# controllera.net
KiCad netlist of a schematic drawn in EAGLE
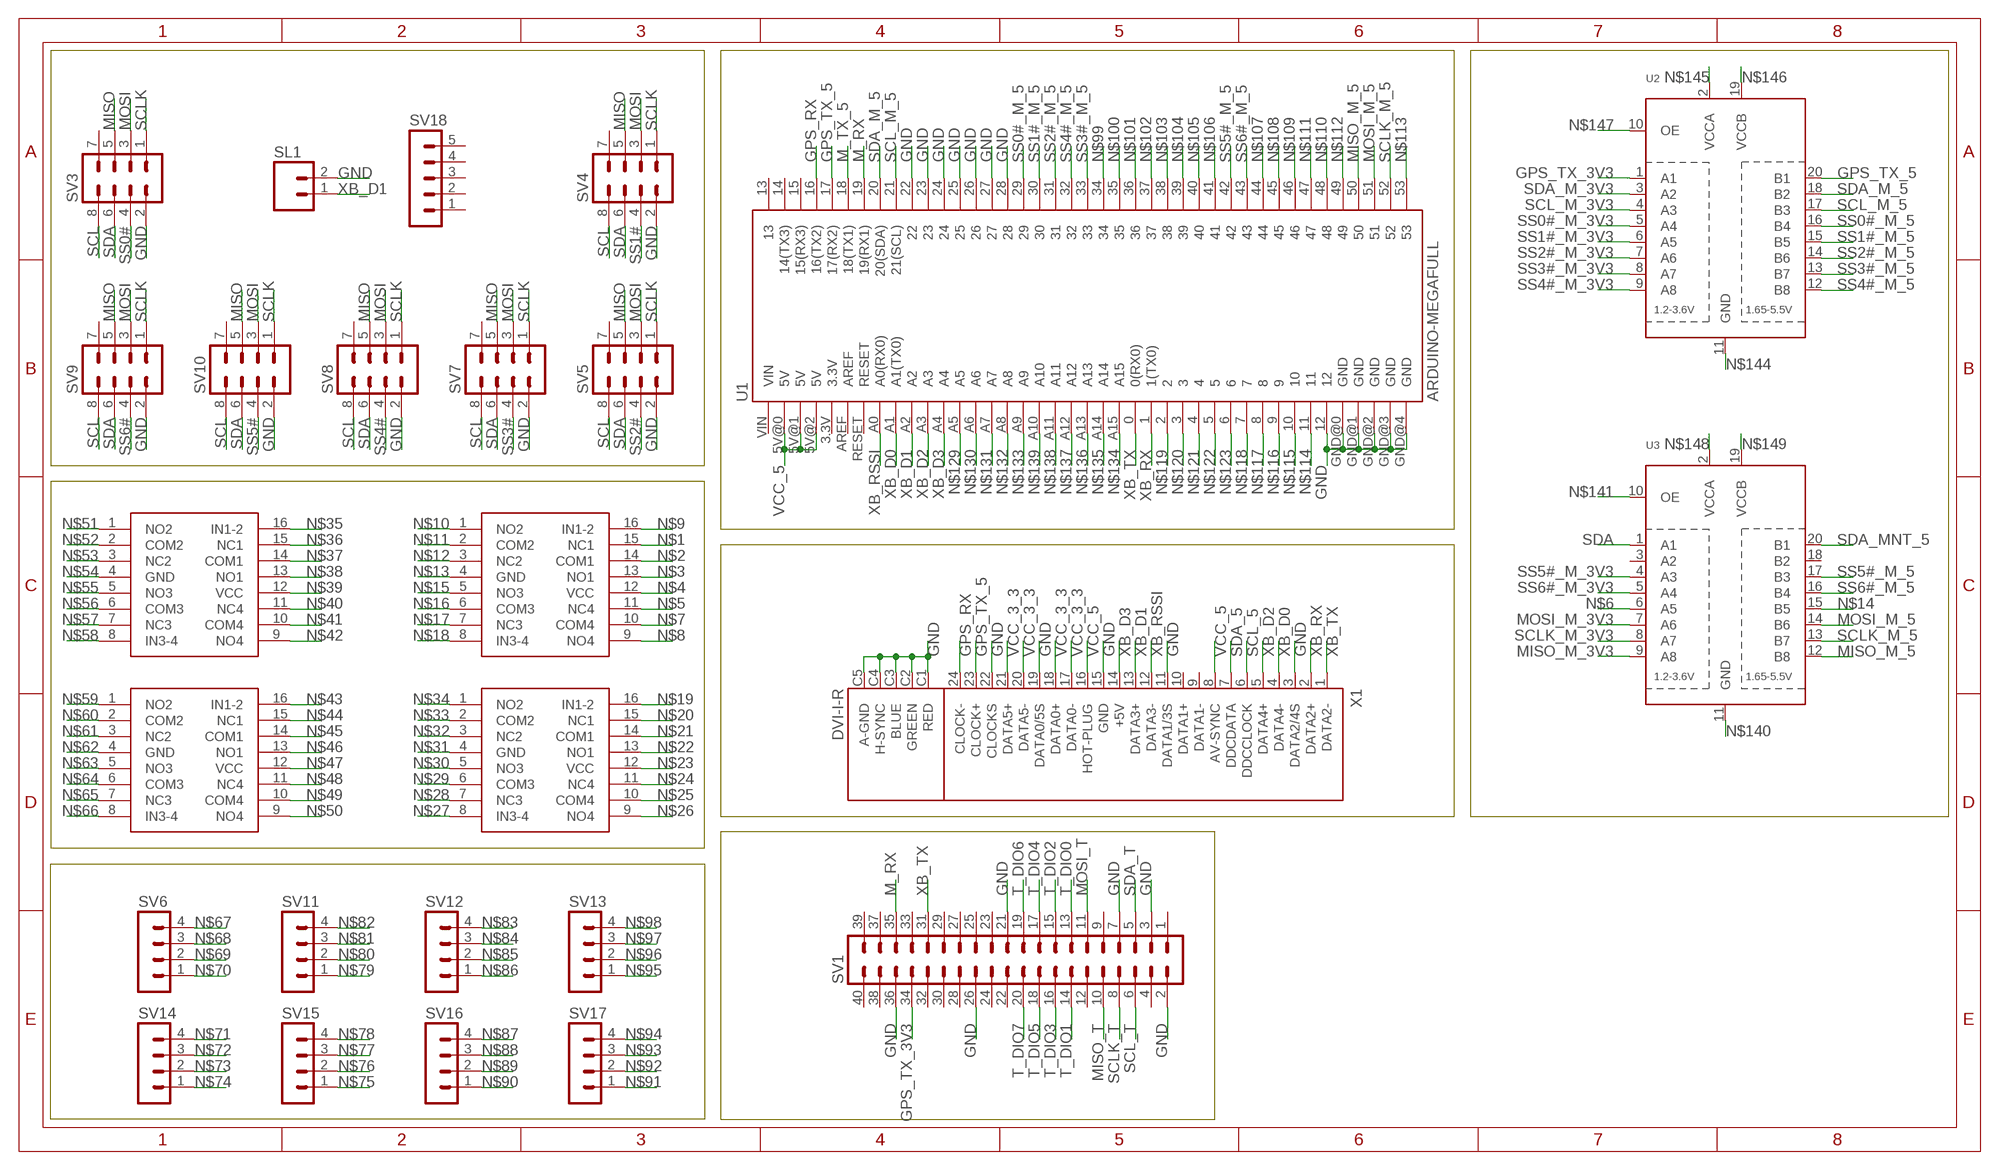
[diagram p0: schematic, sheet 1]

(export (version "E")
  (design (tool "Eeschema 10.0.6"))
  (components
    (comp (ref "SL1")
      (value "MA02")
      (footprint "eagle-import:02PA")
      (libsource (lib "eagle-import") (part "MA02"))
    )
    (comp (ref "SV1")
      (value "MA20-2")
      (footprint "eagle-import:MA20-2")
      (libsource (lib "eagle-import") (part "MA20-2"))
    )
    (comp (ref "SV3")
      (value "MA04-2")
      (footprint "eagle-import:MA04-2")
      (libsource (lib "eagle-import") (part "MA04-2"))
    )
    (comp (ref "SV4")
      (value "MA04-2")
      (footprint "eagle-import:MA04-2")
      (libsource (lib "eagle-import") (part "MA04-2"))
    )
    (comp (ref "SV5")
      (value "MA04-2")
      (footprint "eagle-import:MA04-2")
      (libsource (lib "eagle-import") (part "MA04-2"))
    )
    (comp (ref "SV6")
      (value "MA04-1")
      (footprint "eagle-import:MA04-1")
      (libsource (lib "eagle-import") (part "MA04-1"))
    )
    (comp (ref "SV7")
      (value "MA04-2")
      (footprint "eagle-import:MA04-2")
      (libsource (lib "eagle-import") (part "MA04-2"))
    )
    (comp (ref "SV8")
      (value "MA04-2")
      (footprint "eagle-import:MA04-2")
      (libsource (lib "eagle-import") (part "MA04-2"))
    )
    (comp (ref "SV9")
      (value "MA04-2")
      (footprint "eagle-import:MA04-2")
      (libsource (lib "eagle-import") (part "MA04-2"))
    )
    (comp (ref "SV10")
      (value "MA04-2")
      (footprint "eagle-import:MA04-2")
      (libsource (lib "eagle-import") (part "MA04-2"))
    )
    (comp (ref "SV11")
      (value "MA04-1")
      (footprint "eagle-import:MA04-1")
      (libsource (lib "eagle-import") (part "MA04-1"))
    )
    (comp (ref "SV12")
      (value "MA04-1")
      (footprint "eagle-import:MA04-1")
      (libsource (lib "eagle-import") (part "MA04-1"))
    )
    (comp (ref "SV13")
      (value "MA04-1")
      (footprint "eagle-import:MA04-1")
      (libsource (lib "eagle-import") (part "MA04-1"))
    )
    (comp (ref "SV14")
      (value "MA04-1")
      (footprint "eagle-import:MA04-1")
      (libsource (lib "eagle-import") (part "MA04-1"))
    )
    (comp (ref "SV15")
      (value "MA04-1")
      (footprint "eagle-import:MA04-1")
      (libsource (lib "eagle-import") (part "MA04-1"))
    )
    (comp (ref "SV16")
      (value "MA04-1")
      (footprint "eagle-import:MA04-1")
      (libsource (lib "eagle-import") (part "MA04-1"))
    )
    (comp (ref "SV17")
      (value "MA04-1")
      (footprint "eagle-import:MA04-1")
      (libsource (lib "eagle-import") (part "MA04-1"))
    )
    (comp (ref "SV18")
      (value "MA05-1")
      (footprint "eagle-import:MA05-1")
      (libsource (lib "eagle-import") (part "MA05-1"))
    )
    (comp (ref "U$1")
      (value "TS3A44159PWR")
      (footprint "eagle-import:R-PDSO-G16")
      (libsource (lib "eagle-import") (part "TS3A44159PWR"))
    )
    (comp (ref "U$2")
      (value "TS3A44159PWR")
      (footprint "eagle-import:R-PDSO-G16")
      (libsource (lib "eagle-import") (part "TS3A44159PWR"))
    )
    (comp (ref "U$3")
      (value "TS3A44159PWR")
      (footprint "eagle-import:R-PDSO-G16")
      (libsource (lib "eagle-import") (part "TS3A44159PWR"))
    )
    (comp (ref "U$4")
      (value "TS3A44159PWR")
      (footprint "eagle-import:R-PDSO-G16")
      (libsource (lib "eagle-import") (part "TS3A44159PWR"))
    )
    (comp (ref "U1")
      (value "ARDUINO-MEGAFULL")
      (footprint "eagle-import:ARDUINO_MEGA")
      (libsource (lib "eagle-import") (part "ARDUINO-MEGAFULL"))
    )
    (comp (ref "U2")
      (value "TXB0108PWR")
      (footprint "eagle-import:TSSOP20")
      (libsource (lib "eagle-import") (part "TXB0108PWR"))
    )
    (comp (ref "U3")
      (value "TXB0108PWR")
      (footprint "eagle-import:TSSOP20")
      (libsource (lib "eagle-import") (part "TXB0108PWR"))
    )
    (comp (ref "X1")
      (value "DVI-I-R")
      (footprint "eagle-import:DVI-I-R")
      (libsource (lib "eagle-import") (part "DVI-I-R"))
    )
  )
  (nets
    (net (code "1") (name "/GND") (class "Default")
      (node (ref "SL1") (pin "2") (pinfunction "2_2") (pintype "passive"))
      (node (ref "SV1") (pin "2") (pinfunction "2_2") (pintype "passive"))
      (node (ref "SV1") (pin "21") (pinfunction "21_21") (pintype "passive"))
      (node (ref "SV1") (pin "26") (pinfunction "26_26") (pintype "passive"))
      (node (ref "SV1") (pin "3") (pinfunction "3_3") (pintype "passive"))
      (node (ref "SV1") (pin "36") (pinfunction "36_36") (pintype "passive"))
      (node (ref "SV1") (pin "7") (pinfunction "7_7") (pintype "passive"))
      (node (ref "SV10") (pin "2") (pinfunction "2_2") (pintype "passive"))
      (node (ref "SV3") (pin "2") (pinfunction "2_2") (pintype "passive"))
      (node (ref "SV4") (pin "2") (pinfunction "2_2") (pintype "passive"))
      (node (ref "SV5") (pin "2") (pinfunction "2_2") (pintype "passive"))
      (node (ref "SV7") (pin "2") (pinfunction "2_2") (pintype "passive"))
      (node (ref "SV8") (pin "2") (pinfunction "2_2") (pintype "passive"))
      (node (ref "SV9") (pin "2") (pinfunction "2_2") (pintype "passive"))
      (node (ref "U1") (pin "12") (pinfunction "12_12") (pintype "bidirectional"))
      (node (ref "U1") (pin "22") (pinfunction "22_22") (pintype "bidirectional"))
      (node (ref "U1") (pin "23") (pinfunction "23_23") (pintype "bidirectional"))
      (node (ref "U1") (pin "24") (pinfunction "24_24") (pintype "bidirectional"))
      (node (ref "U1") (pin "25") (pinfunction "25_25") (pintype "bidirectional"))
      (node (ref "U1") (pin "26") (pinfunction "26_26") (pintype "bidirectional"))
      (node (ref "U1") (pin "27") (pinfunction "27_27") (pintype "bidirectional"))
      (node (ref "U1") (pin "28") (pinfunction "28_28") (pintype "bidirectional"))
      (node (ref "U1") (pin "GND@0") (pinfunction "GND_GND@0") (pintype "bidirectional"))
      (node (ref "U1") (pin "GND@1") (pinfunction "GND_GND@1") (pintype "bidirectional"))
      (node (ref "U1") (pin "GND@2") (pinfunction "GND_GND@2") (pintype "bidirectional"))
      (node (ref "U1") (pin "GND@3") (pinfunction "GND_GND@3") (pintype "bidirectional"))
      (node (ref "U1") (pin "GND@4") (pinfunction "GND_GND@4") (pintype "bidirectional"))
      (node (ref "X1") (pin "11") (pinfunction "DATA1/3S_11") (pintype "passive"))
      (node (ref "X1") (pin "15") (pinfunction "GND_15") (pintype "power_in"))
      (node (ref "X1") (pin "19") (pinfunction "DATA0/5S_19") (pintype "passive"))
      (node (ref "X1") (pin "22") (pinfunction "CLOCKS_22") (pintype "passive"))
      (node (ref "X1") (pin "3") (pinfunction "DATA2/4S_3") (pintype "passive"))
      (node (ref "X1") (pin "C1") (pinfunction "RED_C1") (pintype "passive"))
      (node (ref "X1") (pin "C2") (pinfunction "GREEN_C2") (pintype "passive"))
      (node (ref "X1") (pin "C3") (pinfunction "BLUE_C3") (pintype "passive"))
      (node (ref "X1") (pin "C4") (pinfunction "H-SYNC_C4") (pintype "passive"))
      (node (ref "X1") (pin "C5") (pinfunction "A-GND_C5") (pintype "power_in"))
    )
    (net (code "2") (name "/GPS_RX") (class "Default")
      (node (ref "U1") (pin "16") (pinfunction "16(TX2)_16") (pintype "bidirectional"))
      (node (ref "X1") (pin "24") (pinfunction "CLOCK-_24") (pintype "passive"))
    )
    (net (code "3") (name "/GPS_TX_3V3") (class "Default")
      (node (ref "SV1") (pin "34") (pinfunction "34_34") (pintype "passive"))
      (node (ref "U2") (pin "1") (pinfunction "A1_1") (pintype "bidirectional"))
    )
    (net (code "4") (name "/GPS_TX_5") (class "Default")
      (node (ref "U1") (pin "17") (pinfunction "17(RX2)_17") (pintype "bidirectional"))
      (node (ref "U2") (pin "20") (pinfunction "B1_20") (pintype "bidirectional"))
      (node (ref "X1") (pin "23") (pinfunction "CLOCK+_23") (pintype "passive"))
    )
    (net (code "5") (name "/MISO") (class "Default")
      (node (ref "SV10") (pin "5") (pinfunction "5_5") (pintype "passive"))
      (node (ref "SV3") (pin "5") (pinfunction "5_5") (pintype "passive"))
      (node (ref "SV4") (pin "5") (pinfunction "5_5") (pintype "passive"))
      (node (ref "SV5") (pin "5") (pinfunction "5_5") (pintype "passive"))
      (node (ref "SV7") (pin "5") (pinfunction "5_5") (pintype "passive"))
      (node (ref "SV8") (pin "5") (pinfunction "5_5") (pintype "passive"))
      (node (ref "SV9") (pin "5") (pinfunction "5_5") (pintype "passive"))
    )
    (net (code "6") (name "/MISO_M_3V3") (class "Default")
      (node (ref "U3") (pin "9") (pinfunction "A8_9") (pintype "bidirectional"))
    )
    (net (code "7") (name "/MISO_M_5") (class "Default")
      (node (ref "U1") (pin "50") (pinfunction "50_50") (pintype "bidirectional"))
      (node (ref "U3") (pin "12") (pinfunction "B8_12") (pintype "bidirectional"))
    )
    (net (code "8") (name "/MISO_T") (class "Default")
      (node (ref "SV1") (pin "10") (pinfunction "10_10") (pintype "passive"))
    )
    (net (code "9") (name "/MOSI") (class "Default")
      (node (ref "SV10") (pin "3") (pinfunction "3_3") (pintype "passive"))
      (node (ref "SV3") (pin "3") (pinfunction "3_3") (pintype "passive"))
      (node (ref "SV4") (pin "3") (pinfunction "3_3") (pintype "passive"))
      (node (ref "SV5") (pin "3") (pinfunction "3_3") (pintype "passive"))
      (node (ref "SV7") (pin "3") (pinfunction "3_3") (pintype "passive"))
      (node (ref "SV8") (pin "3") (pinfunction "3_3") (pintype "passive"))
      (node (ref "SV9") (pin "3") (pinfunction "3_3") (pintype "passive"))
    )
    (net (code "10") (name "/MOSI_M_3V3") (class "Default")
      (node (ref "U3") (pin "7") (pinfunction "A6_7") (pintype "bidirectional"))
    )
    (net (code "11") (name "/MOSI_M_5") (class "Default")
      (node (ref "U1") (pin "51") (pinfunction "51_51") (pintype "bidirectional"))
      (node (ref "U3") (pin "14") (pinfunction "B6_14") (pintype "bidirectional"))
    )
    (net (code "12") (name "/MOSI_T") (class "Default")
      (node (ref "SV1") (pin "11") (pinfunction "11_11") (pintype "passive"))
    )
    (net (code "13") (name "/M_RX") (class "Default")
      (node (ref "SV1") (pin "35") (pinfunction "35_35") (pintype "passive"))
      (node (ref "U1") (pin "19") (pinfunction "19(RX1)_19") (pintype "bidirectional"))
    )
    (net (code "14") (name "/M_TX_5") (class "Default")
      (node (ref "U1") (pin "18") (pinfunction "18(TX1)_18") (pintype "bidirectional"))
    )
    (net (code "15") (name "/N$1") (class "Default")
      (node (ref "U$2") (pin "15") (pinfunction "NC1_15") (pintype "bidirectional"))
    )
    (net (code "16") (name "/N$2") (class "Default")
      (node (ref "U$2") (pin "14") (pinfunction "COM1_14") (pintype "bidirectional"))
    )
    (net (code "17") (name "/N$3") (class "Default")
      (node (ref "U$2") (pin "13") (pinfunction "NO1_13") (pintype "bidirectional"))
    )
    (net (code "18") (name "/N$4") (class "Default")
      (node (ref "U$2") (pin "12") (pinfunction "VCC_12") (pintype "bidirectional"))
    )
    (net (code "19") (name "/N$5") (class "Default")
      (node (ref "U$2") (pin "11") (pinfunction "NC4_11") (pintype "bidirectional"))
    )
    (net (code "20") (name "/N$6") (class "Default")
      (node (ref "U3") (pin "6") (pinfunction "A5_6") (pintype "bidirectional"))
    )
    (net (code "21") (name "/N$7") (class "Default")
      (node (ref "U$2") (pin "10") (pinfunction "COM4_10") (pintype "bidirectional"))
    )
    (net (code "22") (name "/N$8") (class "Default")
      (node (ref "U$2") (pin "9") (pinfunction "NO4_9") (pintype "bidirectional"))
    )
    (net (code "23") (name "/N$9") (class "Default")
      (node (ref "U$2") (pin "16") (pinfunction "IN1-2_16") (pintype "bidirectional"))
    )
    (net (code "24") (name "/N$10") (class "Default")
      (node (ref "U$2") (pin "1") (pinfunction "NO2_1") (pintype "bidirectional"))
    )
    (net (code "25") (name "/N$11") (class "Default")
      (node (ref "U$2") (pin "2") (pinfunction "COM2_2") (pintype "bidirectional"))
    )
    (net (code "26") (name "/N$12") (class "Default")
      (node (ref "U$2") (pin "3") (pinfunction "NC2_3") (pintype "bidirectional"))
    )
    (net (code "27") (name "/N$13") (class "Default")
      (node (ref "U$2") (pin "4") (pinfunction "GND_4") (pintype "bidirectional"))
    )
    (net (code "28") (name "/N$14") (class "Default")
      (node (ref "U3") (pin "15") (pinfunction "B5_15") (pintype "bidirectional"))
    )
    (net (code "29") (name "/N$15") (class "Default")
      (node (ref "U$2") (pin "5") (pinfunction "NO3_5") (pintype "bidirectional"))
    )
    (net (code "30") (name "/N$16") (class "Default")
      (node (ref "U$2") (pin "6") (pinfunction "COM3_6") (pintype "bidirectional"))
    )
    (net (code "31") (name "/N$17") (class "Default")
      (node (ref "U$2") (pin "7") (pinfunction "NC3_7") (pintype "bidirectional"))
    )
    (net (code "32") (name "/N$18") (class "Default")
      (node (ref "U$2") (pin "8") (pinfunction "IN3-4_8") (pintype "bidirectional"))
    )
    (net (code "33") (name "/N$19") (class "Default")
      (node (ref "U$4") (pin "16") (pinfunction "IN1-2_16") (pintype "bidirectional"))
    )
    (net (code "34") (name "/N$20") (class "Default")
      (node (ref "U$4") (pin "15") (pinfunction "NC1_15") (pintype "bidirectional"))
    )
    (net (code "35") (name "/N$21") (class "Default")
      (node (ref "U$4") (pin "14") (pinfunction "COM1_14") (pintype "bidirectional"))
    )
    (net (code "36") (name "/N$22") (class "Default")
      (node (ref "U$4") (pin "13") (pinfunction "NO1_13") (pintype "bidirectional"))
    )
    (net (code "37") (name "/N$23") (class "Default")
      (node (ref "U$4") (pin "12") (pinfunction "VCC_12") (pintype "bidirectional"))
    )
    (net (code "38") (name "/N$24") (class "Default")
      (node (ref "U$4") (pin "11") (pinfunction "NC4_11") (pintype "bidirectional"))
    )
    (net (code "39") (name "/N$25") (class "Default")
      (node (ref "U$4") (pin "10") (pinfunction "COM4_10") (pintype "bidirectional"))
    )
    (net (code "40") (name "/N$26") (class "Default")
      (node (ref "U$4") (pin "9") (pinfunction "NO4_9") (pintype "bidirectional"))
    )
    (net (code "41") (name "/N$27") (class "Default")
      (node (ref "U$4") (pin "8") (pinfunction "IN3-4_8") (pintype "bidirectional"))
    )
    (net (code "42") (name "/N$28") (class "Default")
      (node (ref "U$4") (pin "7") (pinfunction "NC3_7") (pintype "bidirectional"))
    )
    (net (code "43") (name "/N$29") (class "Default")
      (node (ref "U$4") (pin "6") (pinfunction "COM3_6") (pintype "bidirectional"))
    )
    (net (code "44") (name "/N$30") (class "Default")
      (node (ref "U$4") (pin "5") (pinfunction "NO3_5") (pintype "bidirectional"))
    )
    (net (code "45") (name "/N$31") (class "Default")
      (node (ref "U$4") (pin "4") (pinfunction "GND_4") (pintype "bidirectional"))
    )
    (net (code "46") (name "/N$32") (class "Default")
      (node (ref "U$4") (pin "3") (pinfunction "NC2_3") (pintype "bidirectional"))
    )
    (net (code "47") (name "/N$33") (class "Default")
      (node (ref "U$4") (pin "2") (pinfunction "COM2_2") (pintype "bidirectional"))
    )
    (net (code "48") (name "/N$34") (class "Default")
      (node (ref "U$4") (pin "1") (pinfunction "NO2_1") (pintype "bidirectional"))
    )
    (net (code "49") (name "/N$35") (class "Default")
      (node (ref "U$1") (pin "16") (pinfunction "IN1-2_16") (pintype "bidirectional"))
    )
    (net (code "50") (name "/N$36") (class "Default")
      (node (ref "U$1") (pin "15") (pinfunction "NC1_15") (pintype "bidirectional"))
    )
    (net (code "51") (name "/N$37") (class "Default")
      (node (ref "U$1") (pin "14") (pinfunction "COM1_14") (pintype "bidirectional"))
    )
    (net (code "52") (name "/N$38") (class "Default")
      (node (ref "U$1") (pin "13") (pinfunction "NO1_13") (pintype "bidirectional"))
    )
    (net (code "53") (name "/N$39") (class "Default")
      (node (ref "U$1") (pin "12") (pinfunction "VCC_12") (pintype "bidirectional"))
    )
    (net (code "54") (name "/N$40") (class "Default")
      (node (ref "U$1") (pin "11") (pinfunction "NC4_11") (pintype "bidirectional"))
    )
    (net (code "55") (name "/N$41") (class "Default")
      (node (ref "U$1") (pin "10") (pinfunction "COM4_10") (pintype "bidirectional"))
    )
    (net (code "56") (name "/N$42") (class "Default")
      (node (ref "U$1") (pin "9") (pinfunction "NO4_9") (pintype "bidirectional"))
    )
    (net (code "57") (name "/N$43") (class "Default")
      (node (ref "U$3") (pin "16") (pinfunction "IN1-2_16") (pintype "bidirectional"))
    )
    (net (code "58") (name "/N$44") (class "Default")
      (node (ref "U$3") (pin "15") (pinfunction "NC1_15") (pintype "bidirectional"))
    )
    (net (code "59") (name "/N$45") (class "Default")
      (node (ref "U$3") (pin "14") (pinfunction "COM1_14") (pintype "bidirectional"))
    )
    (net (code "60") (name "/N$46") (class "Default")
      (node (ref "U$3") (pin "13") (pinfunction "NO1_13") (pintype "bidirectional"))
    )
    (net (code "61") (name "/N$47") (class "Default")
      (node (ref "U$3") (pin "12") (pinfunction "VCC_12") (pintype "bidirectional"))
    )
    (net (code "62") (name "/N$48") (class "Default")
      (node (ref "U$3") (pin "11") (pinfunction "NC4_11") (pintype "bidirectional"))
    )
    (net (code "63") (name "/N$49") (class "Default")
      (node (ref "U$3") (pin "10") (pinfunction "COM4_10") (pintype "bidirectional"))
    )
    (net (code "64") (name "/N$50") (class "Default")
      (node (ref "U$3") (pin "9") (pinfunction "NO4_9") (pintype "bidirectional"))
    )
    (net (code "65") (name "/N$51") (class "Default")
      (node (ref "U$1") (pin "1") (pinfunction "NO2_1") (pintype "bidirectional"))
    )
    (net (code "66") (name "/N$52") (class "Default")
      (node (ref "U$1") (pin "2") (pinfunction "COM2_2") (pintype "bidirectional"))
    )
    (net (code "67") (name "/N$53") (class "Default")
      (node (ref "U$1") (pin "3") (pinfunction "NC2_3") (pintype "bidirectional"))
    )
    (net (code "68") (name "/N$54") (class "Default")
      (node (ref "U$1") (pin "4") (pinfunction "GND_4") (pintype "bidirectional"))
    )
    (net (code "69") (name "/N$55") (class "Default")
      (node (ref "U$1") (pin "5") (pinfunction "NO3_5") (pintype "bidirectional"))
    )
    (net (code "70") (name "/N$56") (class "Default")
      (node (ref "U$1") (pin "6") (pinfunction "COM3_6") (pintype "bidirectional"))
    )
    (net (code "71") (name "/N$57") (class "Default")
      (node (ref "U$1") (pin "7") (pinfunction "NC3_7") (pintype "bidirectional"))
    )
    (net (code "72") (name "/N$58") (class "Default")
      (node (ref "U$1") (pin "8") (pinfunction "IN3-4_8") (pintype "bidirectional"))
    )
    (net (code "73") (name "/N$59") (class "Default")
      (node (ref "U$3") (pin "1") (pinfunction "NO2_1") (pintype "bidirectional"))
    )
    (net (code "74") (name "/N$60") (class "Default")
      (node (ref "U$3") (pin "2") (pinfunction "COM2_2") (pintype "bidirectional"))
    )
    (net (code "75") (name "/N$61") (class "Default")
      (node (ref "U$3") (pin "3") (pinfunction "NC2_3") (pintype "bidirectional"))
    )
    (net (code "76") (name "/N$62") (class "Default")
      (node (ref "U$3") (pin "4") (pinfunction "GND_4") (pintype "bidirectional"))
    )
    (net (code "77") (name "/N$63") (class "Default")
      (node (ref "U$3") (pin "5") (pinfunction "NO3_5") (pintype "bidirectional"))
    )
    (net (code "78") (name "/N$64") (class "Default")
      (node (ref "U$3") (pin "6") (pinfunction "COM3_6") (pintype "bidirectional"))
    )
    (net (code "79") (name "/N$65") (class "Default")
      (node (ref "U$3") (pin "7") (pinfunction "NC3_7") (pintype "bidirectional"))
    )
    (net (code "80") (name "/N$66") (class "Default")
      (node (ref "U$3") (pin "8") (pinfunction "IN3-4_8") (pintype "bidirectional"))
    )
    (net (code "81") (name "/N$67") (class "Default")
      (node (ref "SV6") (pin "4") (pinfunction "4_4") (pintype "passive"))
    )
    (net (code "82") (name "/N$68") (class "Default")
      (node (ref "SV6") (pin "3") (pinfunction "3_3") (pintype "passive"))
    )
    (net (code "83") (name "/N$69") (class "Default")
      (node (ref "SV6") (pin "2") (pinfunction "2_2") (pintype "passive"))
    )
    (net (code "84") (name "/N$70") (class "Default")
      (node (ref "SV6") (pin "1") (pinfunction "1_1") (pintype "passive"))
    )
    (net (code "85") (name "/N$71") (class "Default")
      (node (ref "SV14") (pin "4") (pinfunction "4_4") (pintype "passive"))
    )
    (net (code "86") (name "/N$72") (class "Default")
      (node (ref "SV14") (pin "3") (pinfunction "3_3") (pintype "passive"))
    )
    (net (code "87") (name "/N$73") (class "Default")
      (node (ref "SV14") (pin "2") (pinfunction "2_2") (pintype "passive"))
    )
    (net (code "88") (name "/N$74") (class "Default")
      (node (ref "SV14") (pin "1") (pinfunction "1_1") (pintype "passive"))
    )
    (net (code "89") (name "/N$75") (class "Default")
      (node (ref "SV15") (pin "1") (pinfunction "1_1") (pintype "passive"))
    )
    (net (code "90") (name "/N$76") (class "Default")
      (node (ref "SV15") (pin "2") (pinfunction "2_2") (pintype "passive"))
    )
    (net (code "91") (name "/N$77") (class "Default")
      (node (ref "SV15") (pin "3") (pinfunction "3_3") (pintype "passive"))
    )
    (net (code "92") (name "/N$78") (class "Default")
      (node (ref "SV15") (pin "4") (pinfunction "4_4") (pintype "passive"))
    )
    (net (code "93") (name "/N$79") (class "Default")
      (node (ref "SV11") (pin "1") (pinfunction "1_1") (pintype "passive"))
    )
    (net (code "94") (name "/N$80") (class "Default")
      (node (ref "SV11") (pin "2") (pinfunction "2_2") (pintype "passive"))
    )
    (net (code "95") (name "/N$81") (class "Default")
      (node (ref "SV11") (pin "3") (pinfunction "3_3") (pintype "passive"))
    )
    (net (code "96") (name "/N$82") (class "Default")
      (node (ref "SV11") (pin "4") (pinfunction "4_4") (pintype "passive"))
    )
    (net (code "97") (name "/N$83") (class "Default")
      (node (ref "SV12") (pin "4") (pinfunction "4_4") (pintype "passive"))
    )
    (net (code "98") (name "/N$84") (class "Default")
      (node (ref "SV12") (pin "3") (pinfunction "3_3") (pintype "passive"))
    )
    (net (code "99") (name "/N$85") (class "Default")
      (node (ref "SV12") (pin "2") (pinfunction "2_2") (pintype "passive"))
    )
    (net (code "100") (name "/N$86") (class "Default")
      (node (ref "SV12") (pin "1") (pinfunction "1_1") (pintype "passive"))
    )
    (net (code "101") (name "/N$87") (class "Default")
      (node (ref "SV16") (pin "4") (pinfunction "4_4") (pintype "passive"))
    )
    (net (code "102") (name "/N$88") (class "Default")
      (node (ref "SV16") (pin "3") (pinfunction "3_3") (pintype "passive"))
    )
    (net (code "103") (name "/N$89") (class "Default")
      (node (ref "SV16") (pin "2") (pinfunction "2_2") (pintype "passive"))
    )
    (net (code "104") (name "/N$90") (class "Default")
      (node (ref "SV16") (pin "1") (pinfunction "1_1") (pintype "passive"))
    )
    (net (code "105") (name "/N$91") (class "Default")
      (node (ref "SV17") (pin "1") (pinfunction "1_1") (pintype "passive"))
    )
    (net (code "106") (name "/N$92") (class "Default")
      (node (ref "SV17") (pin "2") (pinfunction "2_2") (pintype "passive"))
    )
    (net (code "107") (name "/N$93") (class "Default")
      (node (ref "SV17") (pin "3") (pinfunction "3_3") (pintype "passive"))
    )
    (net (code "108") (name "/N$94") (class "Default")
      (node (ref "SV17") (pin "4") (pinfunction "4_4") (pintype "passive"))
    )
    (net (code "109") (name "/N$95") (class "Default")
      (node (ref "SV13") (pin "1") (pinfunction "1_1") (pintype "passive"))
    )
    (net (code "110") (name "/N$96") (class "Default")
      (node (ref "SV13") (pin "2") (pinfunction "2_2") (pintype "passive"))
    )
    (net (code "111") (name "/N$97") (class "Default")
      (node (ref "SV13") (pin "3") (pinfunction "3_3") (pintype "passive"))
    )
    (net (code "112") (name "/N$98") (class "Default")
      (node (ref "SV13") (pin "4") (pinfunction "4_4") (pintype "passive"))
    )
    (net (code "113") (name "/N$99") (class "Default")
      (node (ref "U1") (pin "34") (pinfunction "34_34") (pintype "bidirectional"))
    )
    (net (code "114") (name "/N$100") (class "Default")
      (node (ref "U1") (pin "35") (pinfunction "35_35") (pintype "bidirectional"))
    )
    (net (code "115") (name "/N$101") (class "Default")
      (node (ref "U1") (pin "36") (pinfunction "36_36") (pintype "bidirectional"))
    )
    (net (code "116") (name "/N$102") (class "Default")
      (node (ref "U1") (pin "37") (pinfunction "37_37") (pintype "bidirectional"))
    )
    (net (code "117") (name "/N$103") (class "Default")
      (node (ref "U1") (pin "38") (pinfunction "38_38") (pintype "bidirectional"))
    )
    (net (code "118") (name "/N$104") (class "Default")
      (node (ref "U1") (pin "39") (pinfunction "39_39") (pintype "bidirectional"))
    )
    (net (code "119") (name "/N$105") (class "Default")
      (node (ref "U1") (pin "40") (pinfunction "40_40") (pintype "bidirectional"))
    )
    (net (code "120") (name "/N$106") (class "Default")
      (node (ref "U1") (pin "41") (pinfunction "41_41") (pintype "bidirectional"))
    )
    (net (code "121") (name "/N$107") (class "Default")
      (node (ref "U1") (pin "44") (pinfunction "44_44") (pintype "bidirectional"))
    )
    (net (code "122") (name "/N$108") (class "Default")
      (node (ref "U1") (pin "45") (pinfunction "45_45") (pintype "bidirectional"))
    )
    (net (code "123") (name "/N$109") (class "Default")
      (node (ref "U1") (pin "46") (pinfunction "46_46") (pintype "bidirectional"))
    )
    (net (code "124") (name "/N$110") (class "Default")
      (node (ref "U1") (pin "48") (pinfunction "48_48") (pintype "bidirectional"))
    )
    (net (code "125") (name "/N$111") (class "Default")
      (node (ref "U1") (pin "47") (pinfunction "47_47") (pintype "bidirectional"))
    )
    (net (code "126") (name "/N$112") (class "Default")
      (node (ref "U1") (pin "49") (pinfunction "49_49") (pintype "bidirectional"))
    )
    (net (code "127") (name "/N$113") (class "Default")
      (node (ref "U1") (pin "53") (pinfunction "53_53") (pintype "bidirectional"))
    )
    (net (code "128") (name "/N$114") (class "Default")
      (node (ref "U1") (pin "11") (pinfunction "11_11") (pintype "bidirectional"))
    )
    (net (code "129") (name "/N$115") (class "Default")
      (node (ref "U1") (pin "10") (pinfunction "10_10") (pintype "bidirectional"))
    )
    (net (code "130") (name "/N$116") (class "Default")
      (node (ref "U1") (pin "9") (pinfunction "9_9") (pintype "bidirectional"))
    )
    (net (code "131") (name "/N$117") (class "Default")
      (node (ref "U1") (pin "8") (pinfunction "8_8") (pintype "bidirectional"))
    )
    (net (code "132") (name "/N$118") (class "Default")
      (node (ref "U1") (pin "7") (pinfunction "7_7") (pintype "bidirectional"))
    )
    (net (code "133") (name "/N$119") (class "Default")
      (node (ref "U1") (pin "2") (pinfunction "2_2") (pintype "bidirectional"))
    )
    (net (code "134") (name "/N$120") (class "Default")
      (node (ref "U1") (pin "3") (pinfunction "3_3") (pintype "bidirectional"))
    )
    (net (code "135") (name "/N$121") (class "Default")
      (node (ref "U1") (pin "4") (pinfunction "4_4") (pintype "bidirectional"))
    )
    (net (code "136") (name "/N$122") (class "Default")
      (node (ref "U1") (pin "5") (pinfunction "5_5") (pintype "bidirectional"))
    )
    (net (code "137") (name "/N$123") (class "Default")
      (node (ref "U1") (pin "6") (pinfunction "6_6") (pintype "bidirectional"))
    )
    (net (code "138") (name "/N$129") (class "Default")
      (node (ref "U1") (pin "A5") (pinfunction "A5_A5") (pintype "bidirectional"))
    )
    (net (code "139") (name "/N$130") (class "Default")
      (node (ref "U1") (pin "A6") (pinfunction "A6_A6") (pintype "bidirectional"))
    )
    (net (code "140") (name "/N$131") (class "Default")
      (node (ref "U1") (pin "A7") (pinfunction "A7_A7") (pintype "bidirectional"))
    )
    (net (code "141") (name "/N$132") (class "Default")
      (node (ref "U1") (pin "A8") (pinfunction "A8_A8") (pintype "bidirectional"))
    )
    (net (code "142") (name "/N$133") (class "Default")
      (node (ref "U1") (pin "A9") (pinfunction "A9_A9") (pintype "bidirectional"))
    )
    (net (code "143") (name "/N$134") (class "Default")
      (node (ref "U1") (pin "A15") (pinfunction "A15_A15") (pintype "bidirectional"))
    )
    (net (code "144") (name "/N$135") (class "Default")
      (node (ref "U1") (pin "A14") (pinfunction "A14_A14") (pintype "bidirectional"))
    )
    (net (code "145") (name "/N$136") (class "Default")
      (node (ref "U1") (pin "A13") (pinfunction "A13_A13") (pintype "bidirectional"))
    )
    (net (code "146") (name "/N$137") (class "Default")
      (node (ref "U1") (pin "A12") (pinfunction "A12_A12") (pintype "bidirectional"))
    )
    (net (code "147") (name "/N$138") (class "Default")
      (node (ref "U1") (pin "A11") (pinfunction "A11_A11") (pintype "bidirectional"))
    )
    (net (code "148") (name "/N$139") (class "Default")
      (node (ref "U1") (pin "A10") (pinfunction "A10_A10") (pintype "bidirectional"))
    )
    (net (code "149") (name "/N$140") (class "Default")
      (node (ref "U3") (pin "11") (pinfunction "GND_11") (pintype "bidirectional"))
    )
    (net (code "150") (name "/N$141") (class "Default")
      (node (ref "U3") (pin "10") (pinfunction "OE_10") (pintype "bidirectional"))
    )
    (net (code "151") (name "/N$144") (class "Default")
      (node (ref "U2") (pin "11") (pinfunction "GND_11") (pintype "bidirectional"))
    )
    (net (code "152") (name "/N$145") (class "Default")
      (node (ref "U2") (pin "2") (pinfunction "VCCA_2") (pintype "bidirectional"))
    )
    (net (code "153") (name "/N$146") (class "Default")
      (node (ref "U2") (pin "19") (pinfunction "VCCB_19") (pintype "bidirectional"))
    )
    (net (code "154") (name "/N$147") (class "Default")
      (node (ref "U2") (pin "10") (pinfunction "OE_10") (pintype "bidirectional"))
    )
    (net (code "155") (name "/N$148") (class "Default")
      (node (ref "U3") (pin "2") (pinfunction "VCCA_2") (pintype "bidirectional"))
    )
    (net (code "156") (name "/N$149") (class "Default")
      (node (ref "U3") (pin "19") (pinfunction "VCCB_19") (pintype "bidirectional"))
    )
    (net (code "157") (name "/SCL") (class "Default")
      (node (ref "SV10") (pin "8") (pinfunction "8_8") (pintype "passive"))
      (node (ref "SV3") (pin "8") (pinfunction "8_8") (pintype "passive"))
      (node (ref "SV4") (pin "8") (pinfunction "8_8") (pintype "passive"))
      (node (ref "SV5") (pin "8") (pinfunction "8_8") (pintype "passive"))
      (node (ref "SV7") (pin "8") (pinfunction "8_8") (pintype "passive"))
      (node (ref "SV8") (pin "8") (pinfunction "8_8") (pintype "passive"))
      (node (ref "SV9") (pin "8") (pinfunction "8_8") (pintype "passive"))
    )
    (net (code "158") (name "/SCLK") (class "Default")
      (node (ref "SV10") (pin "1") (pinfunction "1_1") (pintype "passive"))
      (node (ref "SV3") (pin "1") (pinfunction "1_1") (pintype "passive"))
      (node (ref "SV4") (pin "1") (pinfunction "1_1") (pintype "passive"))
      (node (ref "SV5") (pin "1") (pinfunction "1_1") (pintype "passive"))
      (node (ref "SV7") (pin "1") (pinfunction "1_1") (pintype "passive"))
      (node (ref "SV8") (pin "1") (pinfunction "1_1") (pintype "passive"))
      (node (ref "SV9") (pin "1") (pinfunction "1_1") (pintype "passive"))
    )
    (net (code "159") (name "/SCLK_M_3V3") (class "Default")
      (node (ref "U3") (pin "8") (pinfunction "A7_8") (pintype "bidirectional"))
    )
    (net (code "160") (name "/SCLK_M_5") (class "Default")
      (node (ref "U1") (pin "52") (pinfunction "52_52") (pintype "bidirectional"))
      (node (ref "U3") (pin "13") (pinfunction "B7_13") (pintype "bidirectional"))
    )
    (net (code "161") (name "/SCLK_T") (class "Default")
      (node (ref "SV1") (pin "8") (pinfunction "8_8") (pintype "passive"))
    )
    (net (code "162") (name "/SCL_5") (class "Default")
      (node (ref "X1") (pin "6") (pinfunction "DDCCLOCK_6") (pintype "passive"))
    )
    (net (code "163") (name "/SCL_M_3V3") (class "Default")
      (node (ref "U2") (pin "4") (pinfunction "A3_4") (pintype "bidirectional"))
    )
    (net (code "164") (name "/SCL_M_5") (class "Default")
      (node (ref "U1") (pin "21") (pinfunction "21(SCL)_21") (pintype "bidirectional"))
      (node (ref "U2") (pin "17") (pinfunction "B3_17") (pintype "bidirectional"))
    )
    (net (code "165") (name "/SCL_T") (class "Default")
      (node (ref "SV1") (pin "6") (pinfunction "6_6") (pintype "passive"))
    )
    (net (code "166") (name "/SDA") (class "Default")
      (node (ref "SV10") (pin "6") (pinfunction "6_6") (pintype "passive"))
      (node (ref "SV3") (pin "6") (pinfunction "6_6") (pintype "passive"))
      (node (ref "SV4") (pin "6") (pinfunction "6_6") (pintype "passive"))
      (node (ref "SV5") (pin "6") (pinfunction "6_6") (pintype "passive"))
      (node (ref "SV7") (pin "6") (pinfunction "6_6") (pintype "passive"))
      (node (ref "SV8") (pin "6") (pinfunction "6_6") (pintype "passive"))
      (node (ref "SV9") (pin "6") (pinfunction "6_6") (pintype "passive"))
      (node (ref "U3") (pin "1") (pinfunction "A1_1") (pintype "bidirectional"))
    )
    (net (code "167") (name "/SDA_5") (class "Default")
      (node (ref "X1") (pin "7") (pinfunction "DDCDATA_7") (pintype "passive"))
    )
    (net (code "168") (name "/SDA_MNT_5") (class "Default")
      (node (ref "U3") (pin "20") (pinfunction "B1_20") (pintype "bidirectional"))
    )
    (net (code "169") (name "/SDA_M_3V3") (class "Default")
      (node (ref "U2") (pin "3") (pinfunction "A2_3") (pintype "bidirectional"))
    )
    (net (code "170") (name "/SDA_M_5") (class "Default")
      (node (ref "U1") (pin "20") (pinfunction "20(SDA)_20") (pintype "bidirectional"))
      (node (ref "U2") (pin "18") (pinfunction "B2_18") (pintype "bidirectional"))
    )
    (net (code "171") (name "/SDA_T") (class "Default")
      (node (ref "SV1") (pin "5") (pinfunction "5_5") (pintype "passive"))
    )
    (net (code "172") (name "/SS0#") (class "Default")
      (node (ref "SV3") (pin "4") (pinfunction "4_4") (pintype "passive"))
    )
    (net (code "173") (name "/SS0#_M_3V3") (class "Default")
      (node (ref "U2") (pin "5") (pinfunction "A4_5") (pintype "bidirectional"))
    )
    (net (code "174") (name "/SS0#_M_5") (class "Default")
      (node (ref "U1") (pin "29") (pinfunction "29_29") (pintype "bidirectional"))
      (node (ref "U2") (pin "16") (pinfunction "B4_16") (pintype "bidirectional"))
    )
    (net (code "175") (name "/SS1#") (class "Default")
      (node (ref "SV4") (pin "4") (pinfunction "4_4") (pintype "passive"))
    )
    (net (code "176") (name "/SS1#_M_3V3") (class "Default")
      (node (ref "U2") (pin "6") (pinfunction "A5_6") (pintype "bidirectional"))
    )
    (net (code "177") (name "/SS1#_M_5") (class "Default")
      (node (ref "U1") (pin "30") (pinfunction "30_30") (pintype "bidirectional"))
      (node (ref "U2") (pin "15") (pinfunction "B5_15") (pintype "bidirectional"))
    )
    (net (code "178") (name "/SS2#") (class "Default")
      (node (ref "SV5") (pin "4") (pinfunction "4_4") (pintype "passive"))
    )
    (net (code "179") (name "/SS2#_M_3V3") (class "Default")
      (node (ref "U2") (pin "7") (pinfunction "A6_7") (pintype "bidirectional"))
    )
    (net (code "180") (name "/SS2#_M_5") (class "Default")
      (node (ref "U1") (pin "31") (pinfunction "31_31") (pintype "bidirectional"))
      (node (ref "U2") (pin "14") (pinfunction "B6_14") (pintype "bidirectional"))
    )
    (net (code "181") (name "/SS3#") (class "Default")
      (node (ref "SV7") (pin "4") (pinfunction "4_4") (pintype "passive"))
    )
    (net (code "182") (name "/SS3#_M_3V3") (class "Default")
      (node (ref "U2") (pin "8") (pinfunction "A7_8") (pintype "bidirectional"))
    )
    (net (code "183") (name "/SS3#_M_5") (class "Default")
      (node (ref "U1") (pin "33") (pinfunction "33_33") (pintype "bidirectional"))
      (node (ref "U2") (pin "13") (pinfunction "B7_13") (pintype "bidirectional"))
    )
    (net (code "184") (name "/SS4#") (class "Default")
      (node (ref "SV8") (pin "4") (pinfunction "4_4") (pintype "passive"))
    )
    (net (code "185") (name "/SS4#_M_3V3") (class "Default")
      (node (ref "U2") (pin "9") (pinfunction "A8_9") (pintype "bidirectional"))
    )
    (net (code "186") (name "/SS4#_M_5") (class "Default")
      (node (ref "U1") (pin "32") (pinfunction "32_32") (pintype "bidirectional"))
      (node (ref "U2") (pin "12") (pinfunction "B8_12") (pintype "bidirectional"))
    )
    (net (code "187") (name "/SS5#") (class "Default")
      (node (ref "SV10") (pin "4") (pinfunction "4_4") (pintype "passive"))
    )
    (net (code "188") (name "/SS5#_M_3V3") (class "Default")
      (node (ref "U3") (pin "4") (pinfunction "A3_4") (pintype "bidirectional"))
    )
    (net (code "189") (name "/SS5#_M_5") (class "Default")
      (node (ref "U1") (pin "42") (pinfunction "42_42") (pintype "bidirectional"))
      (node (ref "U3") (pin "17") (pinfunction "B3_17") (pintype "bidirectional"))
    )
    (net (code "190") (name "/SS6#") (class "Default")
      (node (ref "SV9") (pin "4") (pinfunction "4_4") (pintype "passive"))
    )
    (net (code "191") (name "/SS6#_M_3V3") (class "Default")
      (node (ref "U3") (pin "5") (pinfunction "A4_5") (pintype "bidirectional"))
    )
    (net (code "192") (name "/SS6#_M_5") (class "Default")
      (node (ref "U1") (pin "43") (pinfunction "43_43") (pintype "bidirectional"))
      (node (ref "U3") (pin "16") (pinfunction "B4_16") (pintype "bidirectional"))
    )
    (net (code "193") (name "/T_DIO0") (class "Default")
      (node (ref "SV1") (pin "13") (pinfunction "13_13") (pintype "passive"))
    )
    (net (code "194") (name "/T_DIO1") (class "Default")
      (node (ref "SV1") (pin "14") (pinfunction "14_14") (pintype "passive"))
    )
    (net (code "195") (name "/T_DIO2") (class "Default")
      (node (ref "SV1") (pin "15") (pinfunction "15_15") (pintype "passive"))
    )
    (net (code "196") (name "/T_DIO3") (class "Default")
      (node (ref "SV1") (pin "16") (pinfunction "16_16") (pintype "passive"))
    )
    (net (code "197") (name "/T_DIO4") (class "Default")
      (node (ref "SV1") (pin "17") (pinfunction "17_17") (pintype "passive"))
    )
    (net (code "198") (name "/T_DIO5") (class "Default")
      (node (ref "SV1") (pin "18") (pinfunction "18_18") (pintype "passive"))
    )
    (net (code "199") (name "/T_DIO6") (class "Default")
      (node (ref "SV1") (pin "19") (pinfunction "19_19") (pintype "passive"))
    )
    (net (code "200") (name "/T_DIO7") (class "Default")
      (node (ref "SV1") (pin "20") (pinfunction "20_20") (pintype "passive"))
    )
    (net (code "201") (name "/VCC_3_3") (class "Default")
      (node (ref "X1") (pin "17") (pinfunction "DATA0-_17") (pintype "passive"))
      (node (ref "X1") (pin "18") (pinfunction "DATA0+_18") (pintype "passive"))
      (node (ref "X1") (pin "20") (pinfunction "DATA5-_20") (pintype "passive"))
      (node (ref "X1") (pin "21") (pinfunction "DATA5+_21") (pintype "passive"))
    )
    (net (code "202") (name "/VCC_5") (class "Default")
      (node (ref "U1") (pin "5V@0") (pinfunction "5V_5V@0") (pintype "bidirectional"))
      (node (ref "U1") (pin "5V@1") (pinfunction "5V_5V@1") (pintype "bidirectional"))
      (node (ref "U1") (pin "5V@2") (pinfunction "5V_5V@2") (pintype "bidirectional"))
      (node (ref "X1") (pin "16") (pinfunction "HOT-PLUG_16") (pintype "passive"))
      (node (ref "X1") (pin "8") (pinfunction "AV-SYNC_8") (pintype "passive"))
    )
    (net (code "203") (name "/XB_D0") (class "Default")
      (node (ref "U1") (pin "A1") (pinfunction "A1(TX0)_A1") (pintype "bidirectional"))
      (node (ref "X1") (pin "4") (pinfunction "DATA4-_4") (pintype "passive"))
    )
    (net (code "204") (name "/XB_D1") (class "Default")
      (node (ref "SL1") (pin "1") (pinfunction "1_1") (pintype "passive"))
      (node (ref "U1") (pin "A2") (pinfunction "A2_A2") (pintype "bidirectional"))
      (node (ref "X1") (pin "13") (pinfunction "DATA3+_13") (pintype "passive"))
    )
    (net (code "205") (name "/XB_D2") (class "Default")
      (node (ref "U1") (pin "A3") (pinfunction "A3_A3") (pintype "bidirectional"))
      (node (ref "X1") (pin "5") (pinfunction "DATA4+_5") (pintype "passive"))
    )
    (net (code "206") (name "/XB_D3") (class "Default")
      (node (ref "U1") (pin "A4") (pinfunction "A4_A4") (pintype "bidirectional"))
      (node (ref "X1") (pin "14") (pinfunction "+5V_14") (pintype "power_in"))
    )
    (net (code "207") (name "/XB_RSSI") (class "Default")
      (node (ref "U1") (pin "A0") (pinfunction "A0(RX0)_A0") (pintype "bidirectional"))
      (node (ref "X1") (pin "12") (pinfunction "DATA3-_12") (pintype "passive"))
    )
    (net (code "208") (name "/XB_RX") (class "Default")
      (node (ref "U1") (pin "1") (pinfunction "1(TX0)_1") (pintype "bidirectional"))
      (node (ref "X1") (pin "2") (pinfunction "DATA2+_2") (pintype "passive"))
    )
    (net (code "209") (name "/XB_TX") (class "Default")
      (node (ref "SV1") (pin "31") (pinfunction "31_31") (pintype "passive"))
      (node (ref "U1") (pin "0") (pinfunction "0(RX0)_0") (pintype "bidirectional"))
      (node (ref "X1") (pin "1") (pinfunction "DATA2-_1") (pintype "passive"))
    )
    (net (code "210") (name "unconnected-(SV1-Pad1)") (class "Default")
      (node (ref "SV1") (pin "1") (pinfunction "1_1") (pintype "passive"))
    )
    (net (code "211") (name "unconnected-(SV1-Pad4)") (class "Default")
      (node (ref "SV1") (pin "4") (pinfunction "4_4") (pintype "passive"))
    )
    (net (code "212") (name "unconnected-(SV1-Pad9)") (class "Default")
      (node (ref "SV1") (pin "9") (pinfunction "9_9") (pintype "passive"))
    )
    (net (code "213") (name "unconnected-(SV1-Pad12)") (class "Default")
      (node (ref "SV1") (pin "12") (pinfunction "12_12") (pintype "passive"))
    )
    (net (code "214") (name "unconnected-(SV1-Pad22)") (class "Default")
      (node (ref "SV1") (pin "22") (pinfunction "22_22") (pintype "passive"))
    )
    (net (code "215") (name "unconnected-(SV1-Pad23)") (class "Default")
      (node (ref "SV1") (pin "23") (pinfunction "23_23") (pintype "passive"))
    )
    (net (code "216") (name "unconnected-(SV1-Pad24)") (class "Default")
      (node (ref "SV1") (pin "24") (pinfunction "24_24") (pintype "passive"))
    )
    (net (code "217") (name "unconnected-(SV1-Pad25)") (class "Default")
      (node (ref "SV1") (pin "25") (pinfunction "25_25") (pintype "passive"))
    )
    (net (code "218") (name "unconnected-(SV1-Pad27)") (class "Default")
      (node (ref "SV1") (pin "27") (pinfunction "27_27") (pintype "passive"))
    )
    (net (code "219") (name "unconnected-(SV1-Pad28)") (class "Default")
      (node (ref "SV1") (pin "28") (pinfunction "28_28") (pintype "passive"))
    )
    (net (code "220") (name "unconnected-(SV1-Pad29)") (class "Default")
      (node (ref "SV1") (pin "29") (pinfunction "29_29") (pintype "passive"))
    )
    (net (code "221") (name "unconnected-(SV1-Pad30)") (class "Default")
      (node (ref "SV1") (pin "30") (pinfunction "30_30") (pintype "passive"))
    )
    (net (code "222") (name "unconnected-(SV1-Pad32)") (class "Default")
      (node (ref "SV1") (pin "32") (pinfunction "32_32") (pintype "passive"))
    )
    (net (code "223") (name "unconnected-(SV1-Pad33)") (class "Default")
      (node (ref "SV1") (pin "33") (pinfunction "33_33") (pintype "passive"))
    )
    (net (code "224") (name "unconnected-(SV1-Pad37)") (class "Default")
      (node (ref "SV1") (pin "37") (pinfunction "37_37") (pintype "passive"))
    )
    (net (code "225") (name "unconnected-(SV1-Pad38)") (class "Default")
      (node (ref "SV1") (pin "38") (pinfunction "38_38") (pintype "passive"))
    )
    (net (code "226") (name "unconnected-(SV1-Pad39)") (class "Default")
      (node (ref "SV1") (pin "39") (pinfunction "39_39") (pintype "passive"))
    )
    (net (code "227") (name "unconnected-(SV1-Pad40)") (class "Default")
      (node (ref "SV1") (pin "40") (pinfunction "40_40") (pintype "passive"))
    )
    (net (code "228") (name "unconnected-(SV3-Pad7)") (class "Default")
      (node (ref "SV3") (pin "7") (pinfunction "7_7") (pintype "passive"))
    )
    (net (code "229") (name "unconnected-(SV4-Pad7)") (class "Default")
      (node (ref "SV4") (pin "7") (pinfunction "7_7") (pintype "passive"))
    )
    (net (code "230") (name "unconnected-(SV5-Pad7)") (class "Default")
      (node (ref "SV5") (pin "7") (pinfunction "7_7") (pintype "passive"))
    )
    (net (code "231") (name "unconnected-(SV7-Pad7)") (class "Default")
      (node (ref "SV7") (pin "7") (pinfunction "7_7") (pintype "passive"))
    )
    (net (code "232") (name "unconnected-(SV8-Pad7)") (class "Default")
      (node (ref "SV8") (pin "7") (pinfunction "7_7") (pintype "passive"))
    )
    (net (code "233") (name "unconnected-(SV9-Pad7)") (class "Default")
      (node (ref "SV9") (pin "7") (pinfunction "7_7") (pintype "passive"))
    )
    (net (code "234") (name "unconnected-(SV10-Pad7)") (class "Default")
      (node (ref "SV10") (pin "7") (pinfunction "7_7") (pintype "passive"))
    )
    (net (code "235") (name "unconnected-(SV18-Pad1)") (class "Default")
      (node (ref "SV18") (pin "1") (pinfunction "1_1") (pintype "passive"))
    )
    (net (code "236") (name "unconnected-(SV18-Pad2)") (class "Default")
      (node (ref "SV18") (pin "2") (pinfunction "2_2") (pintype "passive"))
    )
    (net (code "237") (name "unconnected-(SV18-Pad3)") (class "Default")
      (node (ref "SV18") (pin "3") (pinfunction "3_3") (pintype "passive"))
    )
    (net (code "238") (name "unconnected-(SV18-Pad4)") (class "Default")
      (node (ref "SV18") (pin "4") (pinfunction "4_4") (pintype "passive"))
    )
    (net (code "239") (name "unconnected-(SV18-Pad5)") (class "Default")
      (node (ref "SV18") (pin "5") (pinfunction "5_5") (pintype "passive"))
    )
    (net (code "240") (name "unconnected-(U1-14(TX3)-Pad14)") (class "Default")
      (node (ref "U1") (pin "14") (pinfunction "14(TX3)_14") (pintype "bidirectional"))
    )
    (net (code "241") (name "unconnected-(U1-15(RX3)-Pad15)") (class "Default")
      (node (ref "U1") (pin "15") (pinfunction "15(RX3)_15") (pintype "bidirectional"))
    )
    (net (code "242") (name "unconnected-(U1-Pad3.3V)") (class "Default")
      (node (ref "U1") (pin "3.3V") (pinfunction "3.3V_3.3V") (pintype "bidirectional"))
    )
    (net (code "243") (name "unconnected-(U1-Pad13)") (class "Default")
      (node (ref "U1") (pin "13") (pinfunction "13_13") (pintype "bidirectional"))
    )
    (net (code "244") (name "unconnected-(U1-PadAREF)") (class "Default")
      (node (ref "U1") (pin "AREF") (pinfunction "AREF_AREF") (pintype "bidirectional"))
    )
    (net (code "245") (name "unconnected-(U1-PadRESET)") (class "Default")
      (node (ref "U1") (pin "RESET") (pinfunction "RESET_RESET") (pintype "bidirectional"))
    )
    (net (code "246") (name "unconnected-(U1-PadVIN)") (class "Default")
      (node (ref "U1") (pin "VIN") (pinfunction "VIN_VIN") (pintype "bidirectional"))
    )
    (net (code "247") (name "unconnected-(U3-A2-Pad3)") (class "Default")
      (node (ref "U3") (pin "3") (pinfunction "A2_3") (pintype "bidirectional"))
    )
    (net (code "248") (name "unconnected-(U3-B2-Pad18)") (class "Default")
      (node (ref "U3") (pin "18") (pinfunction "B2_18") (pintype "bidirectional"))
    )
    (net (code "249") (name "unconnected-(X1B-DATA1+-Pad10)") (class "Default")
      (node (ref "X1") (pin "10") (pinfunction "DATA1+_10") (pintype "passive"))
    )
    (net (code "250") (name "unconnected-(X1B-DATA1--Pad9)") (class "Default")
      (node (ref "X1") (pin "9") (pinfunction "DATA1-_9") (pintype "passive"))
    )
  )
)
